# Fiber_interlock.net
KiCad netlist of a schematic drawn in Altium Designer
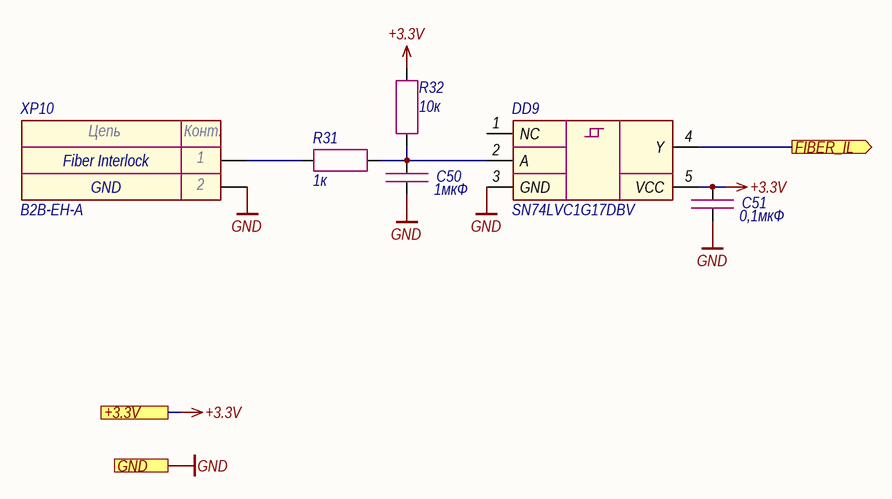
[diagram p0: Fiber_interlock.SchDoc]

(export (version "E")
  (design (tool "Eeschema 10.0.6"))
  (components
    (comp (ref "C50")
      (value "1мкФ")
      (footprint "Pcb_library:CAP_0603")
      (fields (field (name "MANUFACTURER") "Murata"))
      (libsource (lib "Schem_library") (part "Capacitor"))
    )
    (comp (ref "C51")
      (value "0,1мкФ")
      (footprint "Pcb_library:CAP_0603")
      (fields (field (name "MANUFACTURER") "Murata"))
      (libsource (lib "Schem_library") (part "Capacitor"))
    )
    (comp (ref "DD9")
      (value "SN74LVC1G17DBV")
      (footprint "Pcb_library:SOT-23-5")
      (fields (field (name "MANUFACTURER") "Texas Instruments"))
      (libsource (lib "Schem_library") (part "SN74LVC1G17"))
    )
    (comp (ref "R31")
      (value "1к")
      (footprint "Pcb_library:RES_0603")
      (fields (field (name "MANUFACTURER") "Yageo"))
      (libsource (lib "Schem_library") (part "Resistor"))
    )
    (comp (ref "R32")
      (value "10к")
      (footprint "Pcb_library:RES_0603")
      (fields (field (name "MANUFACTURER") "Yageo"))
      (libsource (lib "Schem_library") (part "Resistor"))
    )
    (comp (ref "XP10")
      (value "B2B-EH-A")
      (footprint "Pcb_library:B2B-EH-A")
      (fields (field (name "MANUFACTURER") "JST"))
      (libsource (lib "Schem_library") (part "Connector-2"))
    )
  )
  (nets
    (net (code "1") (name "+3.3V") (class "Default")
      (node (ref "C51") (pin "1") (pinfunction "1_1") (pintype "passive"))
      (node (ref "DD9") (pin "5") (pinfunction "VCC_5") (pintype "passive"))
      (node (ref "R32") (pin "2") (pinfunction "2_2") (pintype "passive"))
    )
    (net (code "2") (name "/FIBER_IL") (class "Default")
      (node (ref "DD9") (pin "4") (pinfunction "Y_4") (pintype "passive"))
    )
    (net (code "3") (name "GND") (class "Default")
      (node (ref "C50") (pin "2") (pinfunction "2_2") (pintype "passive"))
      (node (ref "C51") (pin "2") (pinfunction "2_2") (pintype "passive"))
      (node (ref "DD9") (pin "3") (pinfunction "GND_3") (pintype "passive"))
      (node (ref "XP10") (pin "2") (pintype "passive"))
    )
    (net (code "4") (name "Net-(DD9-A)") (class "Default")
      (node (ref "C50") (pin "1") (pinfunction "1_1") (pintype "passive"))
      (node (ref "DD9") (pin "2") (pinfunction "A_2") (pintype "passive"))
      (node (ref "R31") (pin "2") (pinfunction "2_2") (pintype "passive"))
      (node (ref "R32") (pin "1") (pinfunction "1_1") (pintype "passive"))
    )
    (net (code "5") (name "Net-(R31-Pad1)") (class "Default")
      (node (ref "R31") (pin "1") (pinfunction "1_1") (pintype "passive"))
      (node (ref "XP10") (pin "1") (pintype "passive"))
    )
    (net (code "6") (name "unconnected-(DD9-NC-Pad1)") (class "Default")
      (node (ref "DD9") (pin "1") (pinfunction "NC_1") (pintype "passive"))
    )
  )
)
